# design.net
KiCad netlist of a schematic drawn in Altium Designer
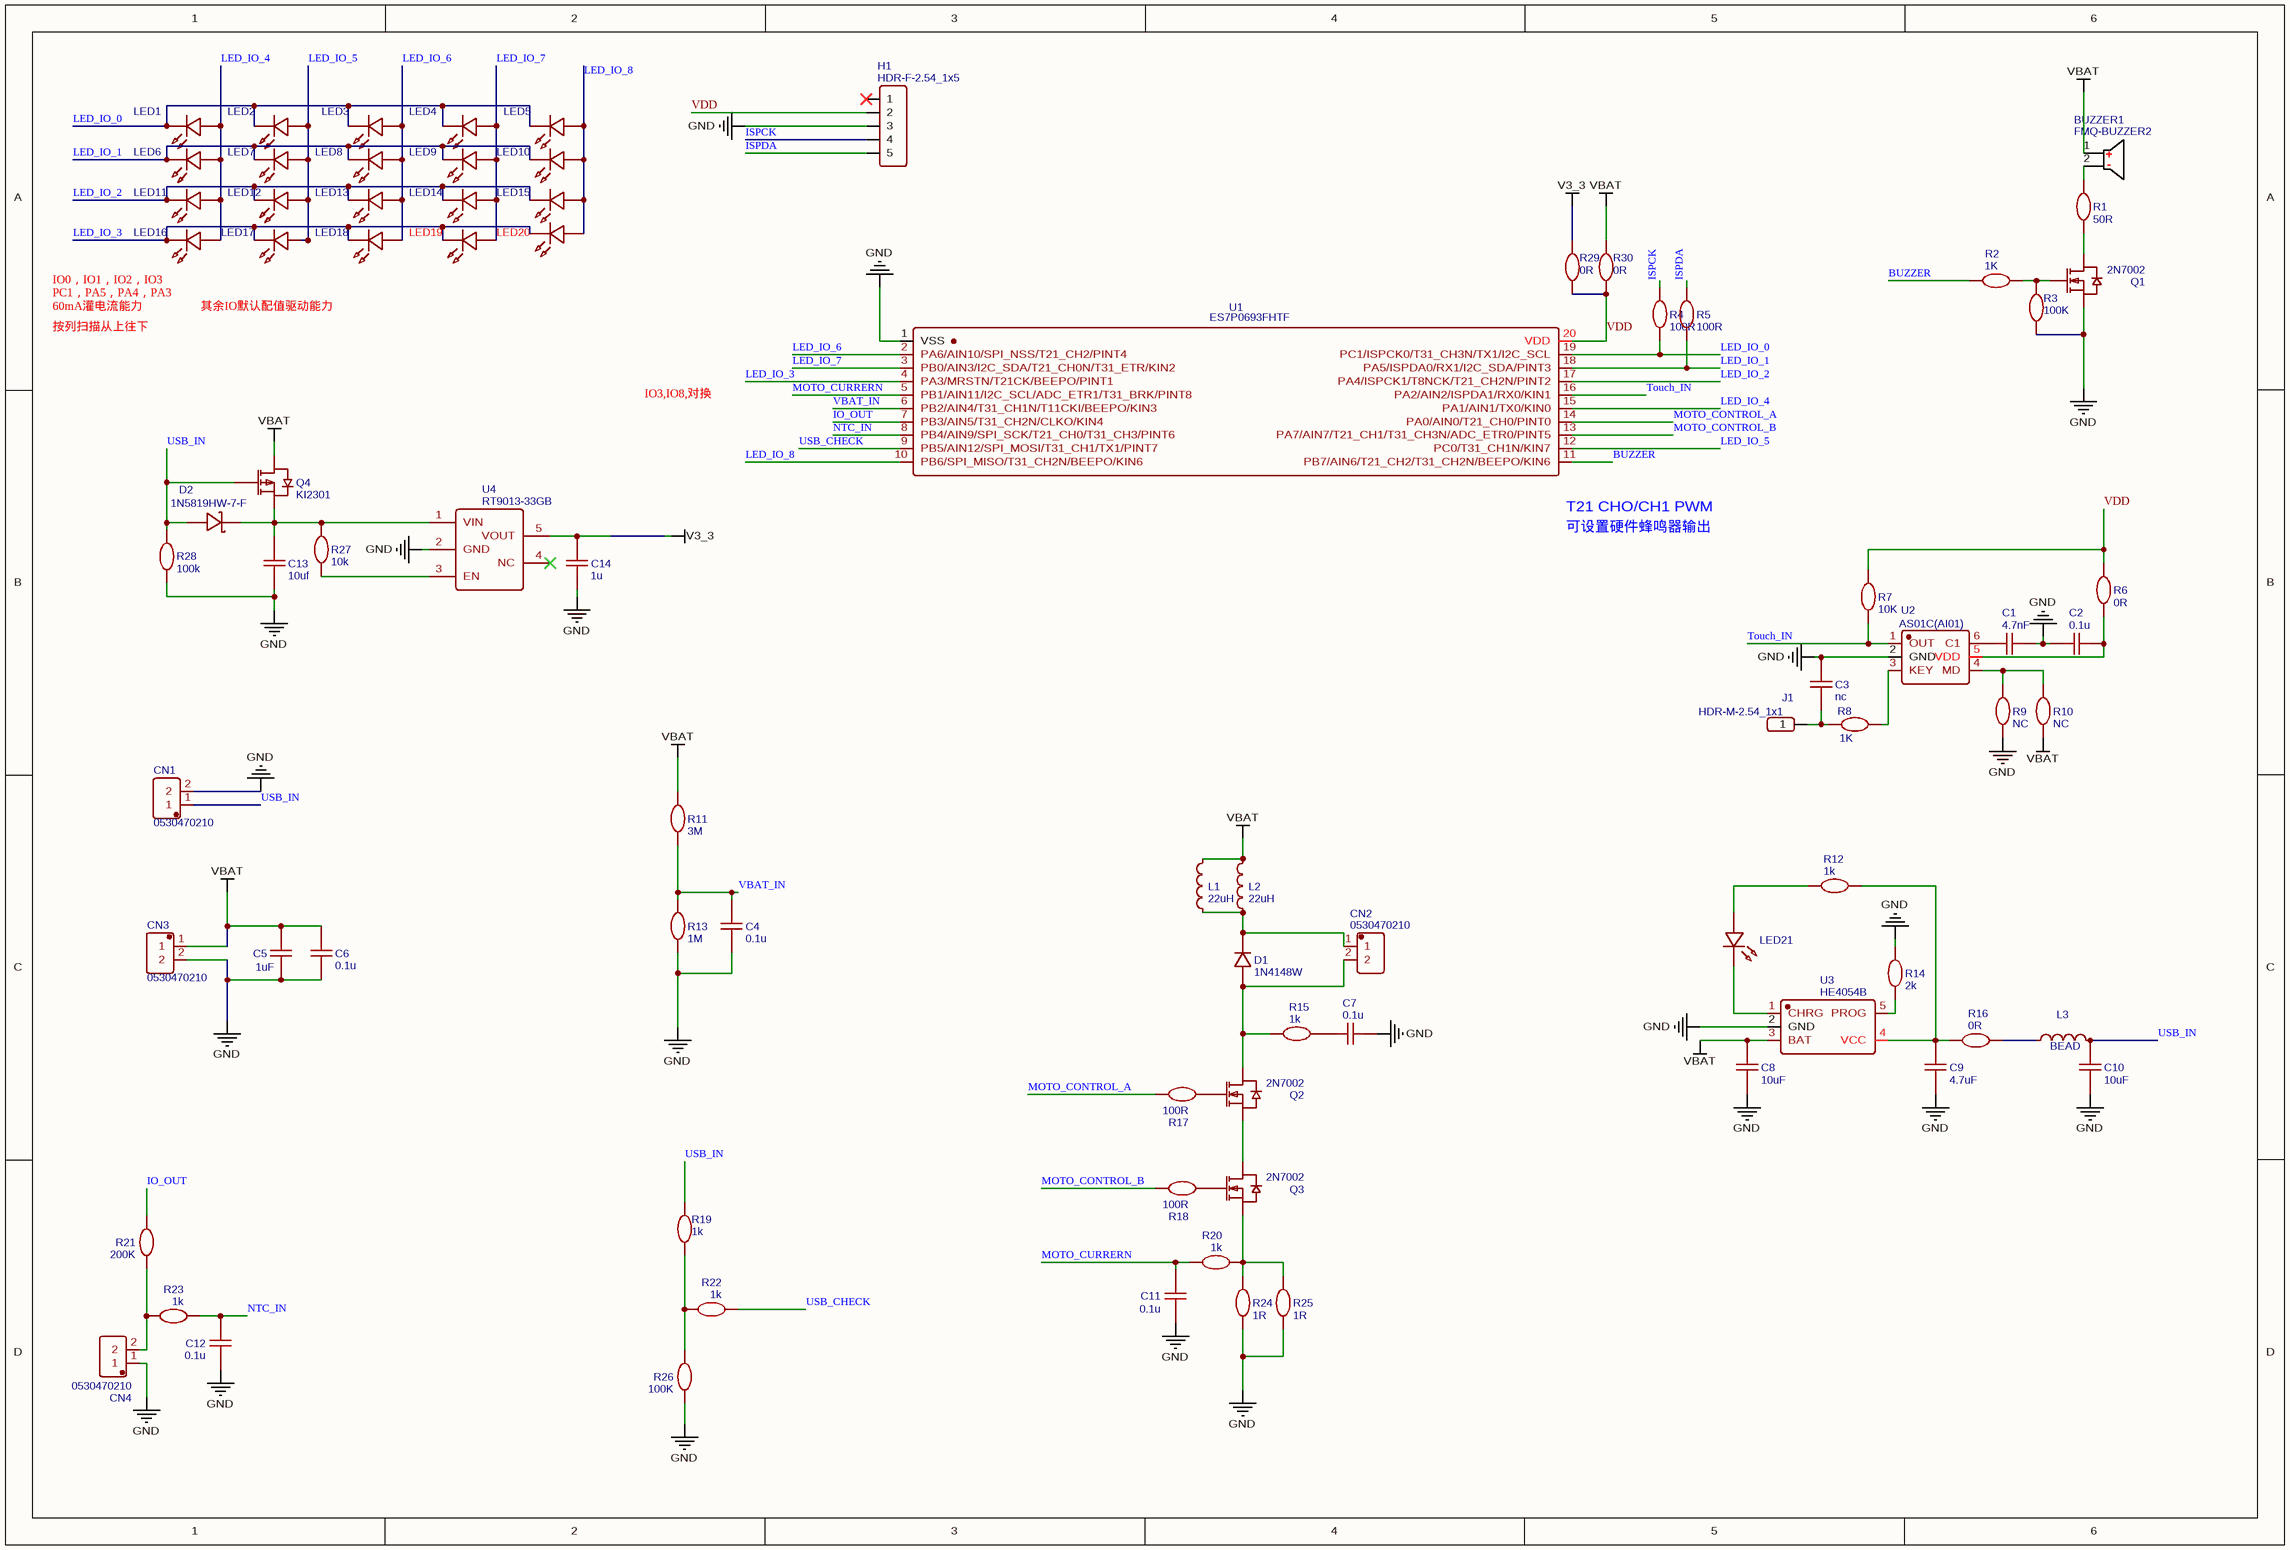
[diagram p0: 搅拌杯原理图.schdoc]

(export (version "E")
  (design (tool "Eeschema 10.0.6"))
  (components
    (comp (ref "BUZZER1")
      (value "FMQ-BUZZER2")
      (footprint "BUZ-TH_BD12.0-P7.60-D0.6-FD")
      (fields (field (name "BOM_SUPPLIER PART") "C9900006103") (field (name "CONTRIBUTOR") "LCSC"))
      (libsource (lib "altium-import") (part "root_0_FMQ-BUZZER2_"))
    )
    (comp (ref "C1")
      (value "4.7nF")
      (footprint "C0603")
      (fields (field (name "CONTRIBUTOR") "LCEDA_Lib"))
      (libsource (lib "altium-import") (part "root_0_4.7nF_"))
    )
    (comp (ref "C2")
      (value "0.1u")
      (footprint "C0603")
      (fields (field (name "CONTRIBUTOR") "LCEDA_Lib"))
      (libsource (lib "altium-import") (part "root_0_0.1u_"))
    )
    (comp (ref "C3")
      (value "nc")
      (footprint "C0603")
      (fields (field (name "CONTRIBUTOR") "LCEDA_Lib"))
      (libsource (lib "altium-import") (part "root_1_nc_"))
    )
    (comp (ref "C4")
      (value "0.1u")
      (footprint "C0603")
      (fields (field (name "CONTRIBUTOR") "LCEDA_Lib"))
      (libsource (lib "altium-import") (part "root_1_0.1u_"))
    )
    (comp (ref "C5")
      (value "1uF")
      (footprint "C0603")
      (fields (field (name "CONTRIBUTOR") "LCEDA_Lib"))
      (libsource (lib "altium-import") (part "root_3_1uF_"))
    )
    (comp (ref "C6")
      (value "0.1u")
      (footprint "C0603")
      (fields (field (name "CONTRIBUTOR") "LCEDA_Lib"))
      (libsource (lib "") (part "root_3_0.1u__1"))
    )
    (comp (ref "C7")
      (value "0.1u")
      (footprint "C0603")
      (fields (field (name "CONTRIBUTOR") "LCEDA_Lib"))
      (libsource (lib "altium-import") (part "root_2_0.1u_"))
    )
    (comp (ref "C8")
      (value "10uF")
      (footprint "C0603")
      (fields (field (name "CONTRIBUTOR") "LCEDA_Lib"))
      (libsource (lib "altium-import") (part "root_1_10uF_"))
    )
    (comp (ref "C9")
      (value "4.7uF")
      (footprint "C0603")
      (fields (field (name "CONTRIBUTOR") "LCEDA_Lib"))
      (libsource (lib "altium-import") (part "root_1_4.7uF_"))
    )
    (comp (ref "C10")
      (value "10uF")
      (footprint "C0603")
      (fields (field (name "CONTRIBUTOR") "LCEDA_Lib"))
      (libsource (lib "altium-import") (part "root_1_10uF_"))
    )
    (comp (ref "C11")
      (value "0.1u")
      (footprint "C0603")
      (fields (field (name "CONTRIBUTOR") "LCEDA_Lib"))
      (libsource (lib "") (part "root_1_0.1u__1"))
    )
    (comp (ref "C12")
      (value "0.1u")
      (footprint "C0603")
      (fields (field (name "CONTRIBUTOR") "LCEDA_Lib"))
      (libsource (lib "altium-import") (part "root_3_0.1u_"))
    )
    (comp (ref "C13")
      (value "10uf")
      (footprint "C0603")
      (fields
        (field (name "BOM_SUPPLIER PART") "C87148")
        (field (name "BOM_MANUFACTURER PART") "JMK105CBJ106MV-F")
        (field (name "CONTRIBUTOR") "LCEDA_Lib")
      )
      (libsource (lib "altium-import") (part "root_1_10uf_"))
    )
    (comp (ref "C14")
      (value "1u")
      (footprint "C0603")
      (fields (field (name "CONTRIBUTOR") "LCEDA_Lib"))
      (libsource (lib "altium-import") (part "root_1_1u_"))
    )
    (comp (ref "CN1")
      (value "0530470210")
      (footprint "CONN-TH_0530470210")
      (fields (field (name "BOM_SUPPLIER PART") "C114130") (field (name "CONTRIBUTOR") "LCSC"))
      (libsource (lib "") (part "root_0_mirrored_0530470210__1"))
    )
    (comp (ref "CN2")
      (value "0530470210")
      (footprint "CONN-TH_0530470210")
      (fields (field (name "BOM_SUPPLIER PART") "C114130") (field (name "CONTRIBUTOR") "LCSC"))
      (libsource (lib "") (part "root_0_0530470210__1"))
    )
    (comp (ref "CN3")
      (value "0530470210")
      (footprint "CONN-TH_0530470210")
      (fields (field (name "BOM_SUPPLIER PART") "C114130") (field (name "CONTRIBUTOR") "LCSC"))
      (libsource (lib "altium-import") (part "root_0_mirrored_0530470210_"))
    )
    (comp (ref "CN4")
      (value "0530470210")
      (footprint "CONN-TH_0530470210")
      (fields (field (name "BOM_SUPPLIER PART") "C114130") (field (name "CONTRIBUTOR") "LCSC"))
      (libsource (lib "altium-import") (part "root_0_0530470210_"))
    )
    (comp (ref "D1")
      (value "1N4148W")
      (footprint "SOD-123FL_L2.6-W1.6-LS3.4-RD")
      (fields (field (name "BOM_SUPPLIER PART") "C129216") (field (name "CONTRIBUTOR") "LCEDA_Lib"))
      (libsource (lib "altium-import") (part "root_1_1N4148W_"))
    )
    (comp (ref "D2")
      (value "1N5819HW-7-F")
      (footprint "SOD-123_L2.8-W1.8-LS3.7-FD")
      (fields (field (name "BOM_SUPPLIER PART") "C82544"))
      (libsource (lib "altium-import") (part "root_0_1N5819HW-7-F_"))
    )
    (comp (ref "H1")
      (value "HDR-F-2.54_1x5")
      (footprint "1.27mm_5PIN")
      (fields (field (name "BOM_SUPPLIER PART") "C50950") (field (name "CONTRIBUTOR") "LCEDA_Lib"))
      (libsource (lib "altium-import") (part "root_0_HDR-F-2.54_1x5_"))
    )
    (comp (ref "J1")
      (value "HDR-M-2.54_1x1")
      (footprint "HDR-M-2.54_1X1")
      (fields (field (name "BOM_SUPPLIER PART") "C81276") (field (name "CONTRIBUTOR") "LCEDA_Lib"))
      (libsource (lib "altium-import") (part "root_2_HDR-M-2.54_1x1_"))
    )
    (comp (ref "L1")
      (value "22uH")
      (footprint "L0603")
      (fields (field (name "CONTRIBUTOR") "LCEDA_Lib"))
      (libsource (lib "altium-import") (part "root_1_22uH_"))
    )
    (comp (ref "L2")
      (value "22uH")
      (footprint "L0603")
      (fields (field (name "CONTRIBUTOR") "LCEDA_Lib"))
      (libsource (lib "altium-import") (part "root_1_22uH_"))
    )
    (comp (ref "L3")
      (value "BEAD")
      (footprint "L0603")
      (fields (field (name "CONTRIBUTOR") "LCEDA_Lib"))
      (libsource (lib "altium-import") (part "root_0_22uH_"))
    )
    (comp (ref "LED1")
      (value "LED-0603_W")
      (footprint "LED0603-FD_WHITE")
      (fields
        (field (name "BOM_MANUFACTURER PART") "17-21SURC/S530-A3/TR8")
        (field (name "BOM_SUPPLIER PART") "C72037")
        (field (name "CONTRIBUTOR") "LCEDA_Lib")
      )
      (libsource (lib "altium-import") (part "root_2_LED-0603_W_"))
    )
    (comp (ref "LED2")
      (value "LED-0603_W")
      (footprint "LED0603-FD_WHITE")
      (fields
        (field (name "BOM_MANUFACTURER PART") "17-21SURC/S530-A3/TR8")
        (field (name "BOM_SUPPLIER PART") "C72037")
        (field (name "CONTRIBUTOR") "LCEDA_Lib")
      )
      (libsource (lib "altium-import") (part "root_2_LED-0603_W_"))
    )
    (comp (ref "LED3")
      (value "LED-0603_W")
      (footprint "LED0603-FD_WHITE")
      (fields
        (field (name "BOM_MANUFACTURER PART") "17-21SURC/S530-A3/TR8")
        (field (name "BOM_SUPPLIER PART") "C72037")
        (field (name "CONTRIBUTOR") "LCEDA_Lib")
      )
      (libsource (lib "altium-import") (part "root_2_LED-0603_W_"))
    )
    (comp (ref "LED4")
      (value "LED-0603_W")
      (footprint "LED0603-FD_WHITE")
      (fields
        (field (name "BOM_MANUFACTURER PART") "17-21SURC/S530-A3/TR8")
        (field (name "BOM_SUPPLIER PART") "C72037")
        (field (name "CONTRIBUTOR") "LCEDA_Lib")
      )
      (libsource (lib "altium-import") (part "root_2_LED-0603_W_"))
    )
    (comp (ref "LED5")
      (value "LED-0603_W")
      (footprint "LED0603-FD_WHITE")
      (fields
        (field (name "BOM_MANUFACTURER PART") "17-21SURC/S530-A3/TR8")
        (field (name "BOM_SUPPLIER PART") "C72037")
        (field (name "CONTRIBUTOR") "LCEDA_Lib")
      )
      (libsource (lib "altium-import") (part "root_2_LED-0603_W_"))
    )
    (comp (ref "LED6")
      (value "LED-0603_W")
      (footprint "LED0603-FD_WHITE")
      (fields
        (field (name "BOM_MANUFACTURER PART") "17-21SURC/S530-A3/TR8")
        (field (name "BOM_SUPPLIER PART") "C72037")
        (field (name "CONTRIBUTOR") "LCEDA_Lib")
      )
      (libsource (lib "altium-import") (part "root_2_LED-0603_W_"))
    )
    (comp (ref "LED7")
      (value "LED-0603_W")
      (footprint "LED0603-FD_WHITE")
      (fields
        (field (name "BOM_MANUFACTURER PART") "17-21SURC/S530-A3/TR8")
        (field (name "BOM_SUPPLIER PART") "C72037")
        (field (name "CONTRIBUTOR") "LCEDA_Lib")
      )
      (libsource (lib "altium-import") (part "root_2_LED-0603_W_"))
    )
    (comp (ref "LED8")
      (value "LED-0603_W")
      (footprint "LED0603-FD_WHITE")
      (fields
        (field (name "BOM_MANUFACTURER PART") "17-21SURC/S530-A3/TR8")
        (field (name "BOM_SUPPLIER PART") "C72037")
        (field (name "CONTRIBUTOR") "LCEDA_Lib")
      )
      (libsource (lib "altium-import") (part "root_2_LED-0603_W_"))
    )
    (comp (ref "LED9")
      (value "LED-0603_W")
      (footprint "LED0603-FD_WHITE")
      (fields
        (field (name "BOM_MANUFACTURER PART") "17-21SURC/S530-A3/TR8")
        (field (name "BOM_SUPPLIER PART") "C72037")
        (field (name "CONTRIBUTOR") "LCEDA_Lib")
      )
      (libsource (lib "altium-import") (part "root_2_LED-0603_W_"))
    )
    (comp (ref "LED10")
      (value "LED-0603_W")
      (footprint "LED0603-FD_WHITE")
      (fields
        (field (name "BOM_MANUFACTURER PART") "17-21SURC/S530-A3/TR8")
        (field (name "BOM_SUPPLIER PART") "C72037")
        (field (name "CONTRIBUTOR") "LCEDA_Lib")
      )
      (libsource (lib "altium-import") (part "root_2_LED-0603_W_"))
    )
    (comp (ref "LED11")
      (value "LED-0603_W")
      (footprint "LED0603-FD_WHITE")
      (fields
        (field (name "BOM_MANUFACTURER PART") "17-21SURC/S530-A3/TR8")
        (field (name "BOM_SUPPLIER PART") "C72037")
        (field (name "CONTRIBUTOR") "LCEDA_Lib")
      )
      (libsource (lib "altium-import") (part "root_2_LED-0603_W_"))
    )
    (comp (ref "LED12")
      (value "LED-0603_W")
      (footprint "LED0603-FD_WHITE")
      (fields
        (field (name "BOM_MANUFACTURER PART") "17-21SURC/S530-A3/TR8")
        (field (name "BOM_SUPPLIER PART") "C72037")
        (field (name "CONTRIBUTOR") "LCEDA_Lib")
      )
      (libsource (lib "altium-import") (part "root_2_LED-0603_W_"))
    )
    (comp (ref "LED13")
      (value "LED-0603_W")
      (footprint "LED0603-FD_WHITE")
      (fields
        (field (name "BOM_MANUFACTURER PART") "17-21SURC/S530-A3/TR8")
        (field (name "BOM_SUPPLIER PART") "C72037")
        (field (name "CONTRIBUTOR") "LCEDA_Lib")
      )
      (libsource (lib "altium-import") (part "root_2_LED-0603_W_"))
    )
    (comp (ref "LED14")
      (value "LED-0603_W")
      (footprint "LED0603-FD_WHITE")
      (fields
        (field (name "BOM_MANUFACTURER PART") "17-21SURC/S530-A3/TR8")
        (field (name "BOM_SUPPLIER PART") "C72037")
        (field (name "CONTRIBUTOR") "LCEDA_Lib")
      )
      (libsource (lib "altium-import") (part "root_2_LED-0603_W_"))
    )
    (comp (ref "LED15")
      (value "LED-0603_W")
      (footprint "LED0603-FD_WHITE")
      (fields
        (field (name "BOM_MANUFACTURER PART") "17-21SURC/S530-A3/TR8")
        (field (name "BOM_SUPPLIER PART") "C72037")
        (field (name "CONTRIBUTOR") "LCEDA_Lib")
      )
      (libsource (lib "altium-import") (part "root_2_LED-0603_W_"))
    )
    (comp (ref "LED16")
      (value "LED-0603_W")
      (footprint "LED0603-FD_WHITE")
      (fields
        (field (name "BOM_MANUFACTURER PART") "17-21SURC/S530-A3/TR8")
        (field (name "BOM_SUPPLIER PART") "C72037")
        (field (name "CONTRIBUTOR") "LCEDA_Lib")
      )
      (libsource (lib "altium-import") (part "root_2_LED-0603_W_"))
    )
    (comp (ref "LED17")
      (value "LED-0603_W")
      (footprint "LED0603-FD_WHITE")
      (fields
        (field (name "BOM_MANUFACTURER PART") "17-21SURC/S530-A3/TR8")
        (field (name "BOM_SUPPLIER PART") "C72037")
        (field (name "CONTRIBUTOR") "LCEDA_Lib")
      )
      (libsource (lib "altium-import") (part "root_2_LED-0603_W_"))
    )
    (comp (ref "LED18")
      (value "LED-0603_W")
      (footprint "LED0603-FD_WHITE")
      (fields
        (field (name "BOM_MANUFACTURER PART") "17-21SURC/S530-A3/TR8")
        (field (name "BOM_SUPPLIER PART") "C72037")
        (field (name "CONTRIBUTOR") "LCEDA_Lib")
      )
      (libsource (lib "altium-import") (part "root_2_LED-0603_W_"))
    )
    (comp (ref "LED19")
      (value "LED-0603_W")
      (footprint "LED0603-FD_WHITE")
      (fields
        (field (name "BOM_MANUFACTURER PART") "17-21SURC/S530-A3/TR8")
        (field (name "BOM_SUPPLIER PART") "C72037")
        (field (name "CONTRIBUTOR") "LCEDA_Lib")
      )
      (libsource (lib "altium-import") (part "root_2_LED-0603_W_"))
    )
    (comp (ref "LED20")
      (value "LED-0603_W")
      (footprint "LED0603-FD_WHITE")
      (fields
        (field (name "BOM_MANUFACTURER PART") "17-21SURC/S530-A3/TR8")
        (field (name "BOM_SUPPLIER PART") "C72037")
        (field (name "CONTRIBUTOR") "LCEDA_Lib")
      )
      (libsource (lib "altium-import") (part "root_2_LED-0603_W_"))
    )
    (comp (ref "LED21")
      (value "LED-0603_W")
      (footprint "LED0603-FD_WHITE")
      (fields
        (field (name "BOM_MANUFACTURER PART") "17-21SURC/S530-A3/TR8")
        (field (name "BOM_SUPPLIER PART") "C72037")
        (field (name "CONTRIBUTOR") "LCEDA_Lib")
      )
      (libsource (lib "altium-import") (part "root_3_LED-0603_W_"))
    )
    (comp (ref "Q1")
      (value "2N7002")
      (footprint "SOT-23_L2.9-W1.3-P0.95-LS2.4-BR")
      (fields
        (field (name "BOM_MANUFACTURER PART") "2N7002,215")
        (field (name "BOM_SUPPLIER PART") "C65189")
        (field (name "CONTRIBUTOR") "LCEDA_Lib")
      )
      (libsource (lib "altium-import") (part "root_2_2N7002_"))
    )
    (comp (ref "Q2")
      (value "2N7002")
      (footprint "SOT-23_L2.9-W1.3-P0.95-LS2.4-BR")
      (fields
        (field (name "BOM_MANUFACTURER PART") "2N7002,215")
        (field (name "BOM_SUPPLIER PART") "C65189")
        (field (name "CONTRIBUTOR") "LCEDA_Lib")
      )
      (libsource (lib "altium-import") (part "root_2_2N7002_"))
    )
    (comp (ref "Q3")
      (value "2N7002")
      (footprint "SOT-23_L2.9-W1.3-P0.95-LS2.4-BR")
      (fields
        (field (name "BOM_MANUFACTURER PART") "2N7002,215")
        (field (name "BOM_SUPPLIER PART") "C65189")
        (field (name "CONTRIBUTOR") "LCEDA_Lib")
      )
      (libsource (lib "altium-import") (part "root_2_2N7002_"))
    )
    (comp (ref "Q4")
      (value "KI2301")
      (footprint "SOT-23-3_L2.9-W1.3-P1.90-LS2.4-BR")
      (fields (field (name "BOM_SUPPLIER PART") "C688914") (field (name "CONTRIBUTOR") "LCSC"))
      (libsource (lib "altium-import") (part "root_0_KI2301_"))
    )
    (comp (ref "R1")
      (value "50R")
      (footprint "R0603")
      (fields (field (name "CONTRIBUTOR") "LCEDA_Lib"))
      (libsource (lib "altium-import") (part "root_3_100R_"))
    )
    (comp (ref "R2")
      (value "1K")
      (footprint "R0603")
      (fields (field (name "CONTRIBUTOR") "LCEDA_Lib"))
      (libsource (lib "altium-import") (part "root_2_1K_"))
    )
    (comp (ref "R3")
      (value "100K")
      (footprint "R0603")
      (fields (field (name "CONTRIBUTOR") "LCEDA_Lib"))
      (libsource (lib "altium-import") (part "root_3_1K_"))
    )
    (comp (ref "R4")
      (value "100R")
      (footprint "R0603")
      (fields (field (name "CONTRIBUTOR") "LCEDA_Lib"))
      (libsource (lib "altium-import") (part "root_3_100R_"))
    )
    (comp (ref "R5")
      (value "100R")
      (footprint "R0603")
      (fields (field (name "CONTRIBUTOR") "LCEDA_Lib"))
      (libsource (lib "altium-import") (part "root_3_100R_"))
    )
    (comp (ref "R6")
      (value "0R")
      (footprint "R0603")
      (fields (field (name "CONTRIBUTOR") "LCEDA_Lib"))
      (libsource (lib "altium-import") (part "root_1_NC_"))
    )
    (comp (ref "R7")
      (value "10K")
      (footprint "R0603")
      (fields (field (name "CONTRIBUTOR") "LCEDA_Lib"))
      (libsource (lib "altium-import") (part "root_1_NC_"))
    )
    (comp (ref "R8")
      (value "1K")
      (footprint "R0603")
      (fields (field (name "CONTRIBUTOR") "LCEDA_Lib"))
      (libsource (lib "altium-import") (part "root_2_1K_"))
    )
    (comp (ref "R9")
      (value "NC")
      (footprint "R0603")
      (fields (field (name "CONTRIBUTOR") "LCEDA_Lib"))
      (libsource (lib "altium-import") (part "root_1_NC_"))
    )
    (comp (ref "R10")
      (value "NC")
      (footprint "R0603")
      (fields (field (name "CONTRIBUTOR") "LCEDA_Lib"))
      (libsource (lib "altium-import") (part "root_1_NC_"))
    )
    (comp (ref "R11")
      (value "3M")
      (footprint "R0603")
      (fields (field (name "CONTRIBUTOR") "LCEDA_Lib"))
      (libsource (lib "altium-import") (part "root_1_430k_"))
    )
    (comp (ref "R12")
      (value "1k")
      (footprint "R0603")
      (fields (field (name "CONTRIBUTOR") "LCEDA_Lib"))
      (libsource (lib "altium-import") (part "root_2_1k_"))
    )
    (comp (ref "R13")
      (value "1M")
      (footprint "R0603")
      (fields (field (name "CONTRIBUTOR") "LCEDA_Lib"))
      (libsource (lib "altium-import") (part "root_1_430K_"))
    )
    (comp (ref "R14")
      (value "2k")
      (footprint "R0603")
      (fields (field (name "CONTRIBUTOR") "LCEDA_Lib"))
      (libsource (lib "altium-import") (part "root_1_1k_"))
    )
    (comp (ref "R15")
      (value "1k")
      (footprint "R0603")
      (fields (field (name "CONTRIBUTOR") "LCEDA_Lib"))
      (libsource (lib "altium-import") (part "root_2_1k_"))
    )
    (comp (ref "R16")
      (value "0R")
      (footprint "R0603")
      (fields (field (name "CONTRIBUTOR") "LCEDA_Lib"))
      (libsource (lib "altium-import") (part "root_0_NC_"))
    )
    (comp (ref "R17")
      (value "100R")
      (footprint "R0603")
      (fields (field (name "CONTRIBUTOR") "LCEDA_Lib"))
      (libsource (lib "altium-import") (part "root_2_100R_"))
    )
    (comp (ref "R18")
      (value "100R")
      (footprint "R0603")
      (fields (field (name "CONTRIBUTOR") "LCEDA_Lib"))
      (libsource (lib "altium-import") (part "root_2_100R_"))
    )
    (comp (ref "R19")
      (value "1k")
      (footprint "R0603")
      (fields (field (name "CONTRIBUTOR") "LCEDA_Lib"))
      (libsource (lib "altium-import") (part "root_3_1k_"))
    )
    (comp (ref "R20")
      (value "1k")
      (footprint "R0603")
      (fields (field (name "CONTRIBUTOR") "LCEDA_Lib"))
      (libsource (lib "altium-import") (part "root_0_1k_"))
    )
    (comp (ref "R21")
      (value "200K")
      (footprint "R0603")
      (fields (field (name "CONTRIBUTOR") "LCEDA_Lib"))
      (libsource (lib "altium-import") (part "root_3_33K_"))
    )
    (comp (ref "R22")
      (value "1k")
      (footprint "R0603")
      (fields (field (name "CONTRIBUTOR") "LCEDA_Lib"))
      (libsource (lib "") (part "root_2_1k__1"))
    )
    (comp (ref "R23")
      (value "1k")
      (footprint "R0603")
      (fields (field (name "CONTRIBUTOR") "LCEDA_Lib"))
      (libsource (lib "") (part "root_2_1k__1"))
    )
    (comp (ref "R24")
      (value "1R")
      (footprint "R1206")
      (fields (field (name "CONTRIBUTOR") "LCEDA_Lib"))
      (libsource (lib "altium-import") (part "root_1_1R_"))
    )
    (comp (ref "R25")
      (value "1R")
      (footprint "R1206")
      (fields (field (name "CONTRIBUTOR") "LCEDA_Lib"))
      (libsource (lib "altium-import") (part "root_1_1R_"))
    )
    (comp (ref "R26")
      (value "100K")
      (footprint "R0603")
      (fields (field (name "CONTRIBUTOR") "LCEDA_Lib"))
      (libsource (lib "altium-import") (part "root_3_33K_"))
    )
    (comp (ref "R27")
      (value "10k")
      (footprint "R0603")
      (fields (field (name "CONTRIBUTOR") "LCEDA_Lib"))
      (libsource (lib "altium-import") (part "root_1_10k_"))
    )
    (comp (ref "R28")
      (value "100k")
      (footprint "C0603")
      (fields (field (name "CONTRIBUTOR") "LCEDA_Lib"))
      (libsource (lib "altium-import") (part "root_1_100k_"))
    )
    (comp (ref "R29")
      (value "0R")
      (footprint "R0603")
      (fields (field (name "CONTRIBUTOR") "LCEDA_Lib"))
      (libsource (lib "altium-import") (part "root_1_NC_"))
    )
    (comp (ref "R30")
      (value "0R")
      (footprint "R0603")
      (fields (field (name "CONTRIBUTOR") "LCEDA_Lib"))
      (libsource (lib "altium-import") (part "root_1_NC_"))
    )
    (comp (ref "U1")
      (value "ES7P0693FHTF")
      (footprint "TSOP20")
      (fields (field (name "CONTRIBUTOR") "zime_zl"))
      (libsource (lib "altium-import") (part "root_0_ES7P0693FHTF_"))
    )
    (comp (ref "U2")
      (value "AS01C(AI01)")
      (footprint "SOT-23-6_L2.9-W1.6-P0.95-LS2.8-BL")
      (fields (field (name "BOM_SUPPLIER PART") "C389617") (field (name "CONTRIBUTOR") "LCSC"))
      (libsource (lib "altium-import") (part "root_0_AS01C(AI01)_"))
    )
    (comp (ref "U3")
      (value "HE4054B")
      (footprint "SOT-23-5_L3.0-W1.7-P0.95-LS2.8-BR")
      (fields (field (name "BOM_SUPPLIER PART") "C711953") (field (name "CONTRIBUTOR") "LCSC"))
      (libsource (lib "altium-import") (part "root_0_HE4054B_"))
    )
    (comp (ref "U4")
      (value "RT9013-33GB")
      (footprint "SOT-23-5_L3.0-W1.7-P0.95-LS2.8-BR")
      (fields (field (name "BOM_SUPPLIER PART") "C47773"))
      (libsource (lib "altium-import") (part "root_0_RT9013-33GB_"))
    )
  )
  (nets
    (net (code "1") (name "/BUZZER") (class "Default")
      (node (ref "R2") (pin "2") (pinfunction "2_2") (pintype "passive"))
      (node (ref "U1") (pin "11") (pinfunction "PB7/AIN6/T21_CH2/T31_CH2N/BEEPO/KIN6_11") (pintype "passive"))
    )
    (net (code "2") (name "/IO_OUT") (class "Default")
      (node (ref "R21") (pin "1") (pinfunction "1_1") (pintype "passive"))
      (node (ref "U1") (pin "7") (pinfunction "PB3/AIN5/T31_CH2N/CLKO/KIN4_7") (pintype "passive"))
    )
    (net (code "3") (name "/ISPCK") (class "Default")
      (node (ref "H1") (pin "4") (pinfunction "4_4") (pintype "passive"))
      (node (ref "R4") (pin "1") (pinfunction "1_1") (pintype "passive"))
    )
    (net (code "4") (name "/ISPDA") (class "Default")
      (node (ref "H1") (pin "5") (pinfunction "5_5") (pintype "passive"))
      (node (ref "R5") (pin "1") (pinfunction "1_1") (pintype "passive"))
    )
    (net (code "5") (name "/LED_IO_0") (class "Default")
      (node (ref "LED1") (pin "2") (pinfunction "2_2") (pintype "passive"))
      (node (ref "LED2") (pin "2") (pinfunction "2_2") (pintype "passive"))
      (node (ref "LED3") (pin "2") (pinfunction "2_2") (pintype "passive"))
      (node (ref "LED4") (pin "2") (pinfunction "2_2") (pintype "passive"))
      (node (ref "LED5") (pin "2") (pinfunction "2_2") (pintype "passive"))
      (node (ref "R4") (pin "2") (pinfunction "2_2") (pintype "passive"))
      (node (ref "U1") (pin "19") (pinfunction "PC1/ISPCK0/T31_CH3N/TX1/I2C_SCL_19") (pintype "passive"))
    )
    (net (code "6") (name "/LED_IO_1") (class "Default")
      (node (ref "LED10") (pin "2") (pinfunction "2_2") (pintype "passive"))
      (node (ref "LED6") (pin "2") (pinfunction "2_2") (pintype "passive"))
      (node (ref "LED7") (pin "2") (pinfunction "2_2") (pintype "passive"))
      (node (ref "LED8") (pin "2") (pinfunction "2_2") (pintype "passive"))
      (node (ref "LED9") (pin "2") (pinfunction "2_2") (pintype "passive"))
      (node (ref "R5") (pin "2") (pinfunction "2_2") (pintype "passive"))
      (node (ref "U1") (pin "18") (pinfunction "PA5/ISPDA0/RX1/I2C_SDA/PINT3_18") (pintype "passive"))
    )
    (net (code "7") (name "/LED_IO_2") (class "Default")
      (node (ref "LED11") (pin "2") (pinfunction "2_2") (pintype "passive"))
      (node (ref "LED12") (pin "2") (pinfunction "2_2") (pintype "passive"))
      (node (ref "LED13") (pin "2") (pinfunction "2_2") (pintype "passive"))
      (node (ref "LED14") (pin "2") (pinfunction "2_2") (pintype "passive"))
      (node (ref "LED15") (pin "2") (pinfunction "2_2") (pintype "passive"))
      (node (ref "U1") (pin "17") (pinfunction "PA4/ISPCK1/T8NCK/T21_CH2N/PINT2_17") (pintype "passive"))
    )
    (net (code "8") (name "/LED_IO_3") (class "Default")
      (node (ref "LED16") (pin "2") (pinfunction "2_2") (pintype "passive"))
      (node (ref "LED17") (pin "2") (pinfunction "2_2") (pintype "passive"))
      (node (ref "LED18") (pin "2") (pinfunction "2_2") (pintype "passive"))
      (node (ref "LED19") (pin "2") (pinfunction "2_2") (pintype "passive"))
      (node (ref "LED20") (pin "2") (pinfunction "2_2") (pintype "passive"))
      (node (ref "U1") (pin "4") (pinfunction "PA3/MRSTN/T21CK/BEEPO/PINT1_4") (pintype "passive"))
    )
    (net (code "9") (name "/LED_IO_4") (class "Default")
      (node (ref "LED1") (pin "1") (pinfunction "1_1") (pintype "passive"))
      (node (ref "LED11") (pin "1") (pinfunction "1_1") (pintype "passive"))
      (node (ref "LED16") (pin "1") (pinfunction "1_1") (pintype "passive"))
      (node (ref "LED6") (pin "1") (pinfunction "1_1") (pintype "passive"))
      (node (ref "U1") (pin "15") (pinfunction "PA1/AIN1/TX0/KIN0_15") (pintype "passive"))
    )
    (net (code "10") (name "/LED_IO_5") (class "Default")
      (node (ref "LED12") (pin "1") (pinfunction "1_1") (pintype "passive"))
      (node (ref "LED17") (pin "1") (pinfunction "1_1") (pintype "passive"))
      (node (ref "LED2") (pin "1") (pinfunction "1_1") (pintype "passive"))
      (node (ref "LED7") (pin "1") (pinfunction "1_1") (pintype "passive"))
      (node (ref "U1") (pin "12") (pinfunction "PC0/T31_CH1N/KIN7_12") (pintype "passive"))
    )
    (net (code "11") (name "/LED_IO_6") (class "Default")
      (node (ref "LED13") (pin "1") (pinfunction "1_1") (pintype "passive"))
      (node (ref "LED18") (pin "1") (pinfunction "1_1") (pintype "passive"))
      (node (ref "LED3") (pin "1") (pinfunction "1_1") (pintype "passive"))
      (node (ref "LED8") (pin "1") (pinfunction "1_1") (pintype "passive"))
      (node (ref "U1") (pin "2") (pinfunction "PA6/AIN10/SPI_NSS/T21_CH2/PINT4_2") (pintype "passive"))
    )
    (net (code "12") (name "/LED_IO_7") (class "Default")
      (node (ref "LED14") (pin "1") (pinfunction "1_1") (pintype "passive"))
      (node (ref "LED19") (pin "1") (pinfunction "1_1") (pintype "passive"))
      (node (ref "LED4") (pin "1") (pinfunction "1_1") (pintype "passive"))
      (node (ref "LED9") (pin "1") (pinfunction "1_1") (pintype "passive"))
      (node (ref "U1") (pin "3") (pinfunction "PB0/AIN3/I2C_SDA/T21_CH0N/T31_ETR/KIN2_3") (pintype "passive"))
    )
    (net (code "13") (name "/LED_IO_8") (class "Default")
      (node (ref "LED10") (pin "1") (pinfunction "1_1") (pintype "passive"))
      (node (ref "LED15") (pin "1") (pinfunction "1_1") (pintype "passive"))
      (node (ref "LED20") (pin "1") (pinfunction "1_1") (pintype "passive"))
      (node (ref "LED5") (pin "1") (pinfunction "1_1") (pintype "passive"))
      (node (ref "U1") (pin "10") (pinfunction "PB6/SPI_MISO/T31_CH2N/BEEPO/KIN6_10") (pintype "passive"))
    )
    (net (code "14") (name "/MOTO_CONTROL_A") (class "Default")
      (node (ref "R17") (pin "1") (pinfunction "1_1") (pintype "passive"))
      (node (ref "U1") (pin "14") (pinfunction "PA0/AIN0/T21_CH0/PINT0_14") (pintype "passive"))
    )
    (net (code "15") (name "/MOTO_CONTROL_B") (class "Default")
      (node (ref "R18") (pin "1") (pinfunction "1_1") (pintype "passive"))
      (node (ref "U1") (pin "13") (pinfunction "PA7/AIN7/T21_CH1/T31_CH3N/ADC_ETR0/PINT5_13") (pintype "passive"))
    )
    (net (code "16") (name "/MOTO_CURRERN") (class "Default")
      (node (ref "C11") (pin "2") (pinfunction "2_2") (pintype "passive"))
      (node (ref "R20") (pin "2") (pinfunction "2_2") (pintype "passive"))
      (node (ref "U1") (pin "5") (pinfunction "PB1/AIN11/I2C_SCL/ADC_ETR1/T31_BRK/PINT8_5") (pintype "passive"))
    )
    (net (code "17") (name "/NTC_IN") (class "Default")
      (node (ref "C12") (pin "1") (pinfunction "1_1") (pintype "passive"))
      (node (ref "R23") (pin "2") (pinfunction "2_2") (pintype "passive"))
      (node (ref "U1") (pin "8") (pinfunction "PB4/AIN9/SPI_SCK/T21_CH0/T31_CH3/PINT6_8") (pintype "passive"))
    )
    (net (code "18") (name "/Touch_IN") (class "Default")
      (node (ref "R7") (pin "1") (pinfunction "1_1") (pintype "passive"))
      (node (ref "U1") (pin "16") (pinfunction "PA2/AIN2/ISPDA1/RX0/KIN1_16") (pintype "passive"))
      (node (ref "U2") (pin "1") (pinfunction "OUT_1") (pintype "passive"))
    )
    (net (code "19") (name "/USB_CHECK") (class "Default")
      (node (ref "R22") (pin "2") (pinfunction "2_2") (pintype "passive"))
      (node (ref "U1") (pin "9") (pinfunction "PB5/AIN12/SPI_MOSI/T31_CH1/TX1/PINT7_9") (pintype "passive"))
    )
    (net (code "20") (name "/USB_IN") (class "Default")
      (node (ref "C10") (pin "2") (pinfunction "2_2") (pintype "passive"))
      (node (ref "CN1") (pin "1") (pinfunction "1_1") (pintype "passive"))
      (node (ref "D2") (pin "1") (pinfunction "A_1") (pintype "passive"))
      (node (ref "L3") (pin "2") (pinfunction "2_2") (pintype "passive"))
      (node (ref "Q4") (pin "1") (pinfunction "G_1") (pintype "passive"))
      (node (ref "R19") (pin "2") (pinfunction "2_2") (pintype "passive"))
      (node (ref "R28") (pin "2") (pinfunction "2_2") (pintype "passive"))
    )
    (net (code "21") (name "/VBAT_IN") (class "Default")
      (node (ref "C4") (pin "2") (pinfunction "2_2") (pintype "passive"))
      (node (ref "R11") (pin "1") (pinfunction "1_1") (pintype "passive"))
      (node (ref "R13") (pin "2") (pinfunction "2_2") (pintype "passive"))
      (node (ref "U1") (pin "6") (pinfunction "PB2/AIN4/T31_CH1N/T11CKI/BEEPO/KIN3_6") (pintype "passive"))
    )
    (net (code "22") (name "/VDD") (class "Default")
      (node (ref "H1") (pin "2") (pinfunction "2_2") (pintype "passive"))
      (node (ref "R29") (pin "1") (pinfunction "1_1") (pintype "passive"))
      (node (ref "R30") (pin "1") (pinfunction "1_1") (pintype "passive"))
      (node (ref "R6") (pin "2") (pinfunction "2_2") (pintype "passive"))
      (node (ref "R7") (pin "2") (pinfunction "2_2") (pintype "passive"))
      (node (ref "U1") (pin "20") (pinfunction "VDD_20") (pintype "passive"))
    )
    (net (code "23") (name "GND") (class "Default")
      (node (ref "C1") (pin "2") (pinfunction "2_2") (pintype "passive"))
      (node (ref "C10") (pin "1") (pinfunction "1_1") (pintype "passive"))
      (node (ref "C11") (pin "1") (pinfunction "1_1") (pintype "passive"))
      (node (ref "C12") (pin "2") (pinfunction "2_2") (pintype "passive"))
      (node (ref "C13") (pin "1") (pinfunction "1_1") (pintype "passive"))
      (node (ref "C14") (pin "1") (pinfunction "1_1") (pintype "passive"))
      (node (ref "C2") (pin "1") (pinfunction "1_1") (pintype "passive"))
      (node (ref "C3") (pin "2") (pinfunction "2_2") (pintype "passive"))
      (node (ref "C4") (pin "1") (pinfunction "1_1") (pintype "passive"))
      (node (ref "C5") (pin "2") (pinfunction "2_2") (pintype "passive"))
      (node (ref "C6") (pin "2") (pinfunction "2_2") (pintype "passive"))
      (node (ref "C7") (pin "1") (pinfunction "1_1") (pintype "passive"))
      (node (ref "C8") (pin "1") (pinfunction "1_1") (pintype "passive"))
      (node (ref "C9") (pin "1") (pinfunction "1_1") (pintype "passive"))
      (node (ref "CN1") (pin "2") (pinfunction "2_2") (pintype "passive"))
      (node (ref "CN3") (pin "2") (pinfunction "2_2") (pintype "passive"))
      (node (ref "CN4") (pin "1") (pinfunction "1_1") (pintype "passive"))
      (node (ref "H1") (pin "3") (pinfunction "3_3") (pintype "passive"))
      (node (ref "Q1") (pin "2") (pinfunction "S_2") (pintype "passive"))
      (node (ref "R13") (pin "1") (pinfunction "1_1") (pintype "passive"))
      (node (ref "R14") (pin "2") (pinfunction "2_2") (pintype "passive"))
      (node (ref "R24") (pin "1") (pinfunction "1_1") (pintype "passive"))
      (node (ref "R25") (pin "1") (pinfunction "1_1") (pintype "passive"))
      (node (ref "R26") (pin "2") (pinfunction "2_2") (pintype "passive"))
      (node (ref "R28") (pin "1") (pinfunction "1_1") (pintype "passive"))
      (node (ref "R3") (pin "2") (pinfunction "2_2") (pintype "passive"))
      (node (ref "R9") (pin "1") (pinfunction "1_1") (pintype "passive"))
      (node (ref "U1") (pin "1") (pinfunction "VSS_1") (pintype "passive"))
      (node (ref "U2") (pin "2") (pinfunction "GND_2") (pintype "passive"))
      (node (ref "U3") (pin "2") (pinfunction "GND_2") (pintype "passive"))
      (node (ref "U4") (pin "2") (pinfunction "GND_2") (pintype "passive"))
    )
    (net (code "24") (name "Net-(BUZZER1-Pad2)") (class "Default")
      (node (ref "BUZZER1") (pin "2") (pinfunction "2_2") (pintype "passive"))
      (node (ref "R1") (pin "1") (pinfunction "1_1") (pintype "passive"))
    )
    (net (code "25") (name "Net-(C3-Pad1)") (class "Default")
      (node (ref "C3") (pin "1") (pinfunction "1_1") (pintype "passive"))
      (node (ref "J1") (pin "1") (pinfunction "1_1") (pintype "passive"))
      (node (ref "R8") (pin "2") (pinfunction "2_2") (pintype "passive"))
    )
    (net (code "26") (name "Net-(C7-Pad2)") (class "Default")
      (node (ref "C7") (pin "2") (pinfunction "2_2") (pintype "passive"))
      (node (ref "R15") (pin "1") (pinfunction "1_1") (pintype "passive"))
    )
    (net (code "27") (name "Net-(CN2-Pad1)") (class "Default")
      (node (ref "CN2") (pin "1") (pinfunction "1_1") (pintype "passive"))
      (node (ref "D1") (pin "1") (pinfunction "1_1") (pintype "passive"))
      (node (ref "L1") (pin "1") (pinfunction "1_1") (pintype "passive"))
      (node (ref "L2") (pin "1") (pinfunction "1_1") (pintype "passive"))
    )
    (net (code "28") (name "Net-(CN4-Pad2)") (class "Default")
      (node (ref "CN4") (pin "2") (pinfunction "2_2") (pintype "passive"))
      (node (ref "R21") (pin "2") (pinfunction "2_2") (pintype "passive"))
      (node (ref "R23") (pin "1") (pinfunction "1_1") (pintype "passive"))
    )
    (net (code "29") (name "Net-(D2-K)") (class "Default")
      (node (ref "C13") (pin "2") (pinfunction "2_2") (pintype "passive"))
      (node (ref "D2") (pin "2") (pinfunction "K_2") (pintype "passive"))
      (node (ref "Q4") (pin "2") (pinfunction "S_2") (pintype "passive"))
      (node (ref "R27") (pin "2") (pinfunction "2_2") (pintype "passive"))
      (node (ref "U4") (pin "1") (pinfunction "VIN_1") (pintype "passive"))
    )
    (net (code "30") (name "Net-(L3-Pad1)") (class "Default")
      (node (ref "L3") (pin "1") (pinfunction "1_1") (pintype "passive"))
      (node (ref "R16") (pin "2") (pinfunction "2_2") (pintype "passive"))
    )
    (net (code "31") (name "Net-(LED21-Pad1)") (class "Default")
      (node (ref "LED21") (pin "1") (pinfunction "1_1") (pintype "passive"))
      (node (ref "R12") (pin "2") (pinfunction "2_2") (pintype "passive"))
    )
    (net (code "32") (name "Net-(Q1-D)") (class "Default")
      (node (ref "Q1") (pin "3") (pinfunction "D_3") (pintype "passive"))
      (node (ref "R1") (pin "2") (pinfunction "2_2") (pintype "passive"))
    )
    (net (code "33") (name "Net-(Q1-G)") (class "Default")
      (node (ref "Q1") (pin "1") (pinfunction "G_1") (pintype "passive"))
      (node (ref "R2") (pin "1") (pinfunction "1_1") (pintype "passive"))
      (node (ref "R3") (pin "1") (pinfunction "1_1") (pintype "passive"))
    )
    (net (code "34") (name "Net-(Q2-D)") (class "Default")
      (node (ref "CN2") (pin "2") (pinfunction "2_2") (pintype "passive"))
      (node (ref "D1") (pin "2") (pinfunction "2_2") (pintype "passive"))
      (node (ref "Q2") (pin "3") (pinfunction "D_3") (pintype "passive"))
      (node (ref "R15") (pin "2") (pinfunction "2_2") (pintype "passive"))
    )
    (net (code "35") (name "Net-(Q2-G)") (class "Default")
      (node (ref "Q2") (pin "1") (pinfunction "G_1") (pintype "passive"))
      (node (ref "R17") (pin "2") (pinfunction "2_2") (pintype "passive"))
    )
    (net (code "36") (name "Net-(Q2-S)") (class "Default")
      (node (ref "Q2") (pin "2") (pinfunction "S_2") (pintype "passive"))
      (node (ref "Q3") (pin "3") (pinfunction "D_3") (pintype "passive"))
    )
    (net (code "37") (name "Net-(Q3-G)") (class "Default")
      (node (ref "Q3") (pin "1") (pinfunction "G_1") (pintype "passive"))
      (node (ref "R18") (pin "2") (pinfunction "2_2") (pintype "passive"))
    )
    (net (code "38") (name "Net-(Q3-S)") (class "Default")
      (node (ref "Q3") (pin "2") (pinfunction "S_2") (pintype "passive"))
      (node (ref "R20") (pin "1") (pinfunction "1_1") (pintype "passive"))
      (node (ref "R24") (pin "2") (pinfunction "2_2") (pintype "passive"))
      (node (ref "R25") (pin "2") (pinfunction "2_2") (pintype "passive"))
    )
    (net (code "39") (name "Net-(R19-Pad1)") (class "Default")
      (node (ref "R19") (pin "1") (pinfunction "1_1") (pintype "passive"))
      (node (ref "R22") (pin "1") (pinfunction "1_1") (pintype "passive"))
      (node (ref "R26") (pin "1") (pinfunction "1_1") (pintype "passive"))
    )
    (net (code "40") (name "Net-(U2-C1)") (class "Default")
      (node (ref "C1") (pin "1") (pinfunction "1_1") (pintype "passive"))
      (node (ref "U2") (pin "6") (pinfunction "C1_6") (pintype "passive"))
    )
    (net (code "41") (name "Net-(U2-KEY)") (class "Default")
      (node (ref "R8") (pin "1") (pinfunction "1_1") (pintype "passive"))
      (node (ref "U2") (pin "3") (pinfunction "KEY_3") (pintype "passive"))
    )
    (net (code "42") (name "Net-(U2-MD)") (class "Default")
      (node (ref "R10") (pin "2") (pinfunction "2_2") (pintype "passive"))
      (node (ref "R9") (pin "2") (pinfunction "2_2") (pintype "passive"))
      (node (ref "U2") (pin "4") (pinfunction "MD_4") (pintype "passive"))
    )
    (net (code "43") (name "Net-(U2-VDD)") (class "Default")
      (node (ref "C2") (pin "2") (pinfunction "2_2") (pintype "passive"))
      (node (ref "R6") (pin "1") (pinfunction "1_1") (pintype "passive"))
      (node (ref "U2") (pin "5") (pinfunction "VDD_5") (pintype "passive"))
    )
    (net (code "44") (name "Net-(U3-CHRG)") (class "Default")
      (node (ref "LED21") (pin "2") (pinfunction "2_2") (pintype "passive"))
      (node (ref "U3") (pin "1") (pinfunction "CHRG_1") (pintype "passive"))
    )
    (net (code "45") (name "Net-(U3-PROG)") (class "Default")
      (node (ref "R14") (pin "1") (pinfunction "1_1") (pintype "passive"))
      (node (ref "U3") (pin "5") (pinfunction "PROG_5") (pintype "passive"))
    )
    (net (code "46") (name "Net-(U3-VCC)") (class "Default")
      (node (ref "C9") (pin "2") (pinfunction "2_2") (pintype "passive"))
      (node (ref "R12") (pin "1") (pinfunction "1_1") (pintype "passive"))
      (node (ref "R16") (pin "1") (pinfunction "1_1") (pintype "passive"))
      (node (ref "U3") (pin "4") (pinfunction "VCC_4") (pintype "passive"))
    )
    (net (code "47") (name "Net-(U4-EN)") (class "Default")
      (node (ref "R27") (pin "1") (pinfunction "1_1") (pintype "passive"))
      (node (ref "U4") (pin "3") (pinfunction "EN_3") (pintype "passive"))
    )
    (net (code "48") (name "V3_3") (class "Default")
      (node (ref "C14") (pin "2") (pinfunction "2_2") (pintype "passive"))
      (node (ref "R29") (pin "2") (pinfunction "2_2") (pintype "passive"))
      (node (ref "U4") (pin "5") (pinfunction "VOUT_5") (pintype "passive"))
    )
    (net (code "49") (name "VBAT") (class "Default")
      (node (ref "BUZZER1") (pin "1") (pinfunction "1_1") (pintype "passive"))
      (node (ref "C5") (pin "1") (pinfunction "1_1") (pintype "passive"))
      (node (ref "C6") (pin "1") (pinfunction "1_1") (pintype "passive"))
      (node (ref "C8") (pin "2") (pinfunction "2_2") (pintype "passive"))
      (node (ref "CN3") (pin "1") (pinfunction "1_1") (pintype "passive"))
      (node (ref "L1") (pin "2") (pinfunction "2_2") (pintype "passive"))
      (node (ref "L2") (pin "2") (pinfunction "2_2") (pintype "passive"))
      (node (ref "Q4") (pin "3") (pinfunction "D_3") (pintype "passive"))
      (node (ref "R10") (pin "1") (pinfunction "1_1") (pintype "passive"))
      (node (ref "R11") (pin "2") (pinfunction "2_2") (pintype "passive"))
      (node (ref "R30") (pin "2") (pinfunction "2_2") (pintype "passive"))
      (node (ref "U3") (pin "3") (pinfunction "BAT_3") (pintype "passive"))
    )
    (net (code "50") (name "unconnected-(H1-Pad1)") (class "Default")
      (node (ref "H1") (pin "1") (pinfunction "1_1") (pintype "passive+no_connect"))
    )
    (net (code "51") (name "unconnected-(U4-NC-Pad4)") (class "Default")
      (node (ref "U4") (pin "4") (pinfunction "NC_4") (pintype "passive+no_connect"))
    )
  )
)
